# VoltageRegulationBoard.net
KiCad netlist of a schematic drawn in EAGLE
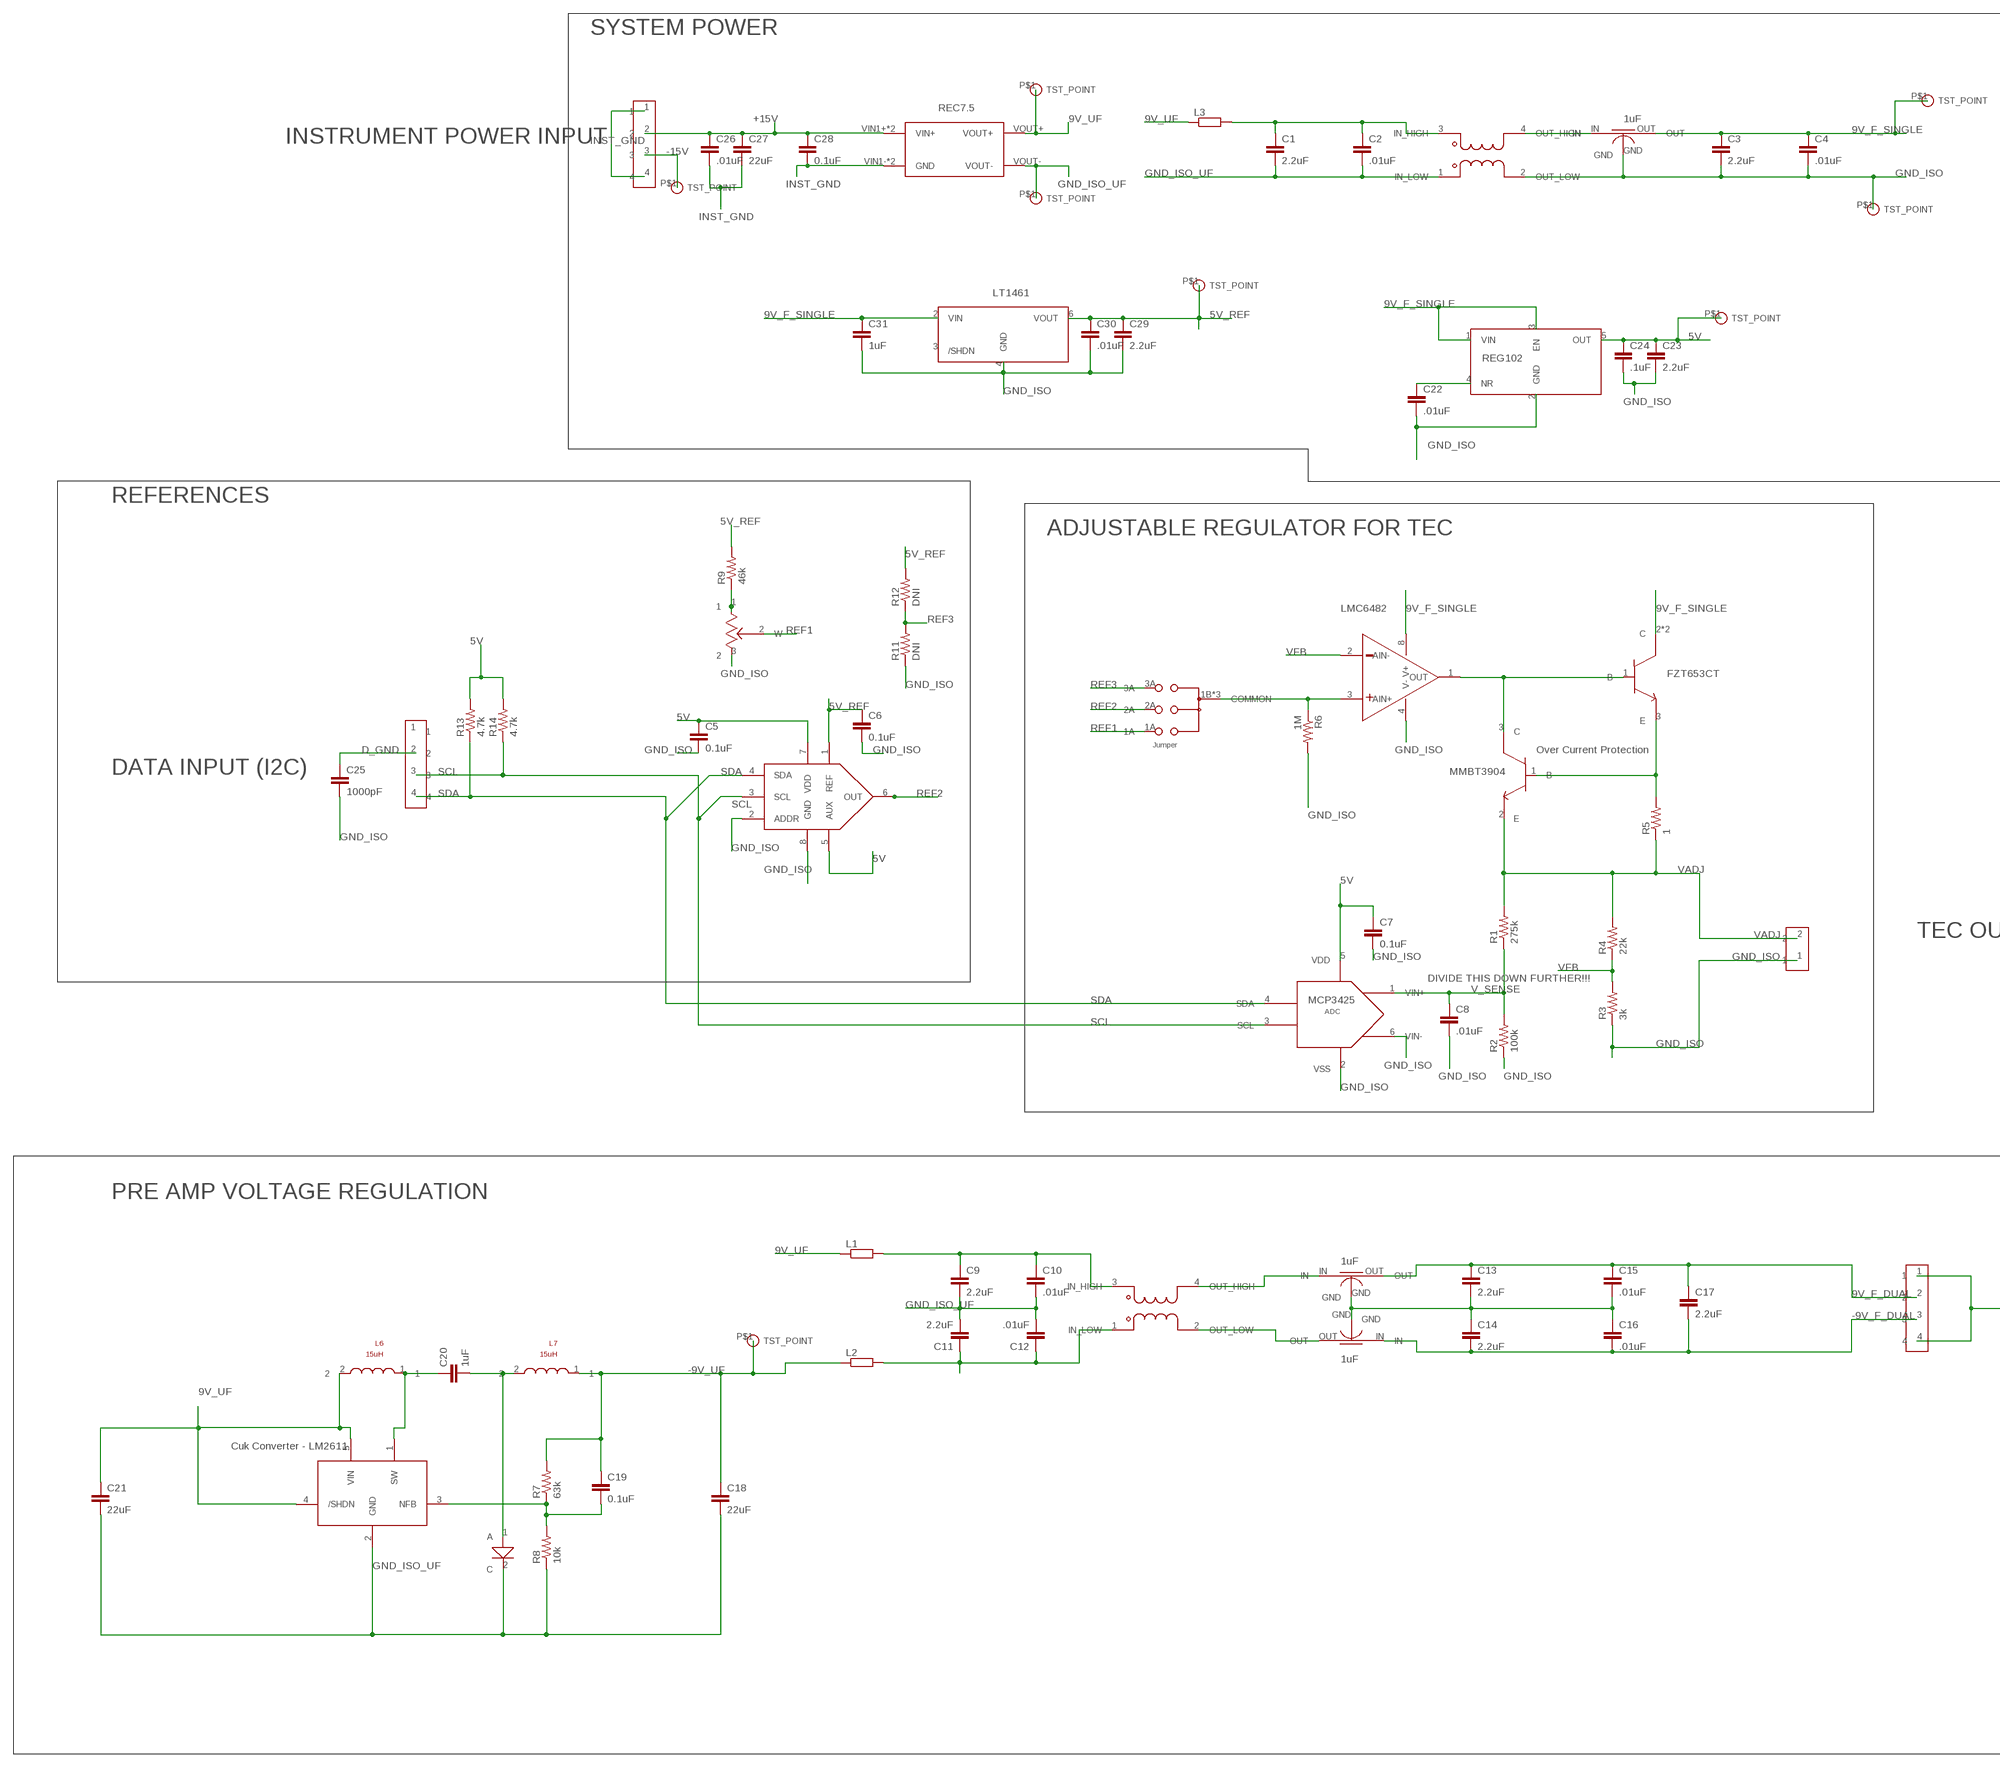
[diagram p0: schematic, sheet 1, part 1 of 2]
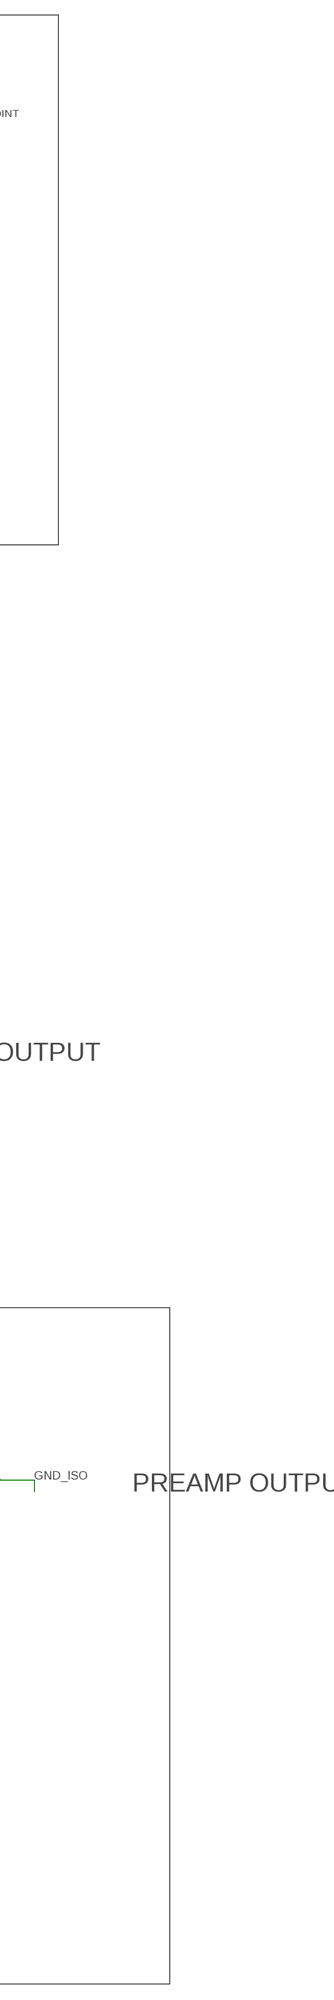
[diagram p1: schematic, sheet 1, part 2 of 2]

(export (version "E")
  (design (tool "Eeschema 10.0.6"))
  (components
    (comp (ref "-9V_U")
      (value "TST_PT")
      (footprint "eagle-import:TST_POINT")
      (libsource (lib "eagle-import") (part "TST_PT"))
    )
    (comp (ref "-15V")
      (value "TST_PT")
      (footprint "eagle-import:TST_POINT")
      (libsource (lib "eagle-import") (part "TST_PT"))
    )
    (comp (ref "5V")
      (value "TST_PT")
      (footprint "eagle-import:TST_POINT")
      (libsource (lib "eagle-import") (part "TST_PT"))
    )
    (comp (ref "9V_F_S")
      (value "TST_PT")
      (footprint "eagle-import:TST_POINT")
      (libsource (lib "eagle-import") (part "TST_PT"))
    )
    (comp (ref "9V_UF")
      (value "TST_PT")
      (footprint "eagle-import:TST_POINT")
      (libsource (lib "eagle-import") (part "TST_PT"))
    )
    (comp (ref "C1")
      (value "2.2uF")
      (footprint "eagle-import:C0603")
      (libsource (lib "eagle-import") (part "C-EUC0603"))
    )
    (comp (ref "C2")
      (value ".01uF")
      (footprint "eagle-import:C0603")
      (libsource (lib "eagle-import") (part "C-EUC0603"))
    )
    (comp (ref "C3")
      (value "2.2uF")
      (footprint "eagle-import:C0603")
      (libsource (lib "eagle-import") (part "C-EUC0603"))
    )
    (comp (ref "C4")
      (value ".01uF")
      (footprint "eagle-import:C0603")
      (libsource (lib "eagle-import") (part "C-EUC0603"))
    )
    (comp (ref "C5")
      (value "0.1uF")
      (footprint "eagle-import:C0603")
      (libsource (lib "eagle-import") (part "C-EUC0603"))
    )
    (comp (ref "C6")
      (value "0.1uF")
      (footprint "eagle-import:C0603")
      (libsource (lib "eagle-import") (part "C-EUC0603"))
    )
    (comp (ref "C7")
      (value "0.1uF")
      (footprint "eagle-import:C0603")
      (libsource (lib "eagle-import") (part "C-EUC0603"))
    )
    (comp (ref "C8")
      (value ".01uF")
      (footprint "eagle-import:C0603")
      (libsource (lib "eagle-import") (part "C-EUC0603"))
    )
    (comp (ref "C9")
      (value "2.2uF")
      (footprint "eagle-import:C0603")
      (libsource (lib "eagle-import") (part "C-EUC0603"))
    )
    (comp (ref "C10")
      (value ".01uF")
      (footprint "eagle-import:C0603")
      (libsource (lib "eagle-import") (part "C-EUC0603"))
    )
    (comp (ref "C11")
      (value "2.2uF")
      (footprint "eagle-import:C0603")
      (libsource (lib "eagle-import") (part "C-EUC0603"))
    )
    (comp (ref "C12")
      (value ".01uF")
      (footprint "eagle-import:C0603")
      (libsource (lib "eagle-import") (part "C-EUC0603"))
    )
    (comp (ref "C13")
      (value "2.2uF")
      (footprint "eagle-import:C0603")
      (libsource (lib "eagle-import") (part "C-EUC0603"))
    )
    (comp (ref "C14")
      (value "2.2uF")
      (footprint "eagle-import:C0603")
      (libsource (lib "eagle-import") (part "C-EUC0603"))
    )
    (comp (ref "C15")
      (value ".01uF")
      (footprint "eagle-import:C0603")
      (libsource (lib "eagle-import") (part "C-EUC0603"))
    )
    (comp (ref "C16")
      (value ".01uF")
      (footprint "eagle-import:C0603")
      (libsource (lib "eagle-import") (part "C-EUC0603"))
    )
    (comp (ref "C17")
      (value "2.2uF")
      (footprint "eagle-import:C0603")
      (libsource (lib "eagle-import") (part "C-EUC0603"))
    )
    (comp (ref "C18")
      (value "22uF")
      (footprint "eagle-import:C1206")
      (libsource (lib "eagle-import") (part "C-EUC1206"))
    )
    (comp (ref "C19")
      (value "0.1uF")
      (footprint "eagle-import:C0603")
      (libsource (lib "eagle-import") (part "C-EUC0603"))
    )
    (comp (ref "C20")
      (value "1uF")
      (footprint "eagle-import:C0603")
      (libsource (lib "eagle-import") (part "C-EUC0603"))
    )
    (comp (ref "C21")
      (value "22uF")
      (footprint "eagle-import:C1206")
      (libsource (lib "eagle-import") (part "C-EUC1206"))
    )
    (comp (ref "C22")
      (value ".01uF")
      (footprint "eagle-import:C0603")
      (libsource (lib "eagle-import") (part "C-EUC0603"))
    )
    (comp (ref "C23")
      (value "2.2uF")
      (footprint "eagle-import:C0603")
      (libsource (lib "eagle-import") (part "C-EUC0603"))
    )
    (comp (ref "C24")
      (value ".1uF")
      (footprint "eagle-import:C0603")
      (libsource (lib "eagle-import") (part "C-EUC0603"))
    )
    (comp (ref "C25")
      (value "1000pF")
      (footprint "eagle-import:C0603")
      (libsource (lib "eagle-import") (part "C-EUC0603"))
    )
    (comp (ref "C26")
      (value ".01uF")
      (footprint "eagle-import:C0603")
      (libsource (lib "eagle-import") (part "C-EUC0603"))
    )
    (comp (ref "C27")
      (value "22uF")
      (footprint "eagle-import:C1206")
      (libsource (lib "eagle-import") (part "C-EUC1206"))
    )
    (comp (ref "C28")
      (value "0.1uF")
      (footprint "eagle-import:C0603")
      (libsource (lib "eagle-import") (part "C-EUC0603"))
    )
    (comp (ref "C29")
      (value "2.2uF")
      (footprint "eagle-import:C0603")
      (libsource (lib "eagle-import") (part "C-EUC0603"))
    )
    (comp (ref "C30")
      (value ".01uF")
      (footprint "eagle-import:C0603")
      (libsource (lib "eagle-import") (part "C-EUC0603"))
    )
    (comp (ref "C31")
      (value "1uF")
      (footprint "eagle-import:C0603")
      (libsource (lib "eagle-import") (part "C-EUC0603"))
    )
    (comp (ref "FC1")
      (value "FEED_THRU_CAP")
      (footprint "eagle-import:3-TERM-CAP")
      (libsource (lib "eagle-import") (part "FEED_THRU_CAP"))
    )
    (comp (ref "FC2")
      (value "FEED_THRU_CAP")
      (footprint "eagle-import:3-TERM-CAP")
      (libsource (lib "eagle-import") (part "FEED_THRU_CAP"))
    )
    (comp (ref "FC3")
      (value "FEED_THRU_CAP")
      (footprint "eagle-import:3-TERM-CAP")
      (libsource (lib "eagle-import") (part "FEED_THRU_CAP"))
    )
    (comp (ref "GND_ISO")
      (value "TST_PT")
      (footprint "eagle-import:TST_POINT")
      (libsource (lib "eagle-import") (part "TST_PT"))
    )
    (comp (ref "GND_ISO_UF")
      (value "TST_PT")
      (footprint "eagle-import:TST_POINT")
      (libsource (lib "eagle-import") (part "TST_PT"))
    )
    (comp (ref "J1")
      (value "4-OUT")
      (footprint "eagle-import:4-THRU")
      (libsource (lib "eagle-import") (part "4-OUT"))
    )
    (comp (ref "J2")
      (value "4-OUT")
      (footprint "eagle-import:4-THRU")
      (libsource (lib "eagle-import") (part "4-OUT"))
    )
    (comp (ref "J3")
      (value "4-OUT")
      (footprint "eagle-import:4-THRU")
      (libsource (lib "eagle-import") (part "4-OUT"))
    )
    (comp (ref "J4")
      (value "2-THRU")
      (footprint "eagle-import:2-THRU-.1")
      (libsource (lib "eagle-import") (part "2-THRU"))
    )
    (comp (ref "L1")
      (value "R-EU_R0603")
      (footprint "eagle-import:R0603")
      (libsource (lib "eagle-import") (part "R-EU_R0603"))
    )
    (comp (ref "L2")
      (value "R-EU_R0603")
      (footprint "eagle-import:R0603")
      (libsource (lib "eagle-import") (part "R-EU_R0603"))
    )
    (comp (ref "L3")
      (value "R-EU_R0603")
      (footprint "eagle-import:R0603")
      (libsource (lib "eagle-import") (part "R-EU_R0603"))
    )
    (comp (ref "L4")
      (value "COMMON_MODE_CHOKE")
      (footprint "eagle-import:COMM_MODE_CHOKE")
      (libsource (lib "eagle-import") (part "COMMON_MODE_CHOKE"))
    )
    (comp (ref "L5")
      (value "COMMON_MODE_CHOKE")
      (footprint "eagle-import:COMM_MODE_CHOKE")
      (libsource (lib "eagle-import") (part "COMMON_MODE_CHOKE"))
    )
    (comp (ref "L6")
      (value "15uH")
      (footprint "eagle-import:INDUCTOR_FOOTPRNT")
      (libsource (lib "eagle-import") (part "INDUCTOR"))
    )
    (comp (ref "L7")
      (value "15uH")
      (footprint "eagle-import:INDUCTOR_FOOTPRNT")
      (libsource (lib "eagle-import") (part "INDUCTOR"))
    )
    (comp (ref "R1")
      (value "275k")
      (footprint "eagle-import:R0603")
      (libsource (lib "eagle-import") (part "R-US_R0603"))
    )
    (comp (ref "R2")
      (value "100k")
      (footprint "eagle-import:R0603")
      (libsource (lib "eagle-import") (part "R-US_R0603"))
    )
    (comp (ref "R3")
      (value "3k")
      (footprint "eagle-import:R0603")
      (libsource (lib "eagle-import") (part "R-US_R0603"))
    )
    (comp (ref "R4")
      (value "22k")
      (footprint "eagle-import:R0603")
      (libsource (lib "eagle-import") (part "R-US_R0603"))
    )
    (comp (ref "R5")
      (value "1")
      (footprint "eagle-import:R2512")
      (libsource (lib "eagle-import") (part "R-US_R2512"))
    )
    (comp (ref "R6")
      (value "1M")
      (footprint "eagle-import:R0603")
      (libsource (lib "eagle-import") (part "R-US_R0603"))
    )
    (comp (ref "R7")
      (value "63k")
      (footprint "eagle-import:R0603")
      (libsource (lib "eagle-import") (part "R-US_R0603"))
    )
    (comp (ref "R8")
      (value "10k")
      (footprint "eagle-import:R0603")
      (libsource (lib "eagle-import") (part "R-US_R0603"))
    )
    (comp (ref "R9")
      (value "46k")
      (footprint "eagle-import:R0603")
      (libsource (lib "eagle-import") (part "R-US_R0603"))
    )
    (comp (ref "R10")
      (value "POTENTIOMETER")
      (footprint "eagle-import:3-THRU")
      (libsource (lib "eagle-import") (part "POTENTIOMETER"))
    )
    (comp (ref "R11")
      (value "DNI")
      (footprint "eagle-import:R0603")
      (libsource (lib "eagle-import") (part "R-US_R0603"))
    )
    (comp (ref "R12")
      (value "DNI")
      (footprint "eagle-import:R0603")
      (libsource (lib "eagle-import") (part "R-US_R0603"))
    )
    (comp (ref "R13")
      (value "4.7k")
      (footprint "eagle-import:R0603")
      (libsource (lib "eagle-import") (part "R-US_R0603"))
    )
    (comp (ref "R14")
      (value "4.7k")
      (footprint "eagle-import:R0603")
      (libsource (lib "eagle-import") (part "R-US_R0603"))
    )
    (comp (ref "T1")
      (value "MMBT3904LT1GOSCT-ND(SMALL-SIGNAL-NMOS)")
      (footprint "eagle-import:SOT23")
      (libsource (lib "eagle-import") (part "MMBT3904LT1GOSCT-ND(SMALL-SIGNAL-NMOS)"))
    )
    (comp (ref "T2")
      (value "FZT653-NPNBJT")
      (footprint "eagle-import:SOT223")
      (libsource (lib "eagle-import") (part "FZT653-NPNBJT"))
    )
    (comp (ref "U$3")
      (value "3XJUMPER")
      (footprint "eagle-import:2-THRU")
      (libsource (lib "eagle-import") (part "3XJUMPER"))
    )
    (comp (ref "U$10")
      (value "SCHOTTKY")
      (footprint "eagle-import:SOD-123")
      (libsource (lib "eagle-import") (part "SCHOTTKY"))
    )
    (comp (ref "U1")
      (value "LMC6482")
      (footprint "eagle-import:SOIC8")
      (libsource (lib "eagle-import") (part "LMC6482"))
    )
    (comp (ref "U2")
      (value "DAC_UMAX")
      (footprint "eagle-import:8-UMAX")
      (libsource (lib "eagle-import") (part "DAC_UMAX"))
    )
    (comp (ref "U3")
      (value "VREF")
      (footprint "eagle-import:SOIC8")
      (libsource (lib "eagle-import") (part "VREF"))
    )
    (comp (ref "U4")
      (value "REC7.5-1209")
      (footprint "eagle-import:REC7.5-1209")
      (libsource (lib "eagle-import") (part "REC7.5-1209"))
    )
    (comp (ref "U5")
      (value "REG102")
      (footprint "eagle-import:SOT-23-5")
      (libsource (lib "eagle-import") (part "REG102"))
    )
    (comp (ref "U6")
      (value "MCP3425A0T-E")
      (footprint "eagle-import:SOT-23-6")
      (libsource (lib "eagle-import") (part "MCP3425A0T-E"))
    )
    (comp (ref "U7")
      (value "LM2611")
      (footprint "eagle-import:SOT-23-5")
      (libsource (lib "eagle-import") (part "LM2611"))
    )
    (comp (ref "VREF")
      (value "TST_PT")
      (footprint "eagle-import:TST_POINT")
      (libsource (lib "eagle-import") (part "TST_PT"))
    )
  )
  (nets
    (net (code "1") (name "/+15V") (class "Default")
      (node (ref "C26") (pin "1") (pinfunction "1_1") (pintype "passive"))
      (node (ref "C27") (pin "1") (pinfunction "1_1") (pintype "passive"))
      (node (ref "C28") (pin "1") (pinfunction "1_1") (pintype "passive"))
      (node (ref "J1") (pin "2") (pinfunction "2_2") (pintype "bidirectional"))
      (node (ref "U4") (pin "VIN1+") (pinfunction "VIN+_VIN1+") (pintype "bidirectional"))
      (node (ref "U4") (pin "VIN2+") (pinfunction "VIN+_VIN2+") (pintype "bidirectional"))
    )
    (net (code "2") (name "/-9V_F_DUAL") (class "Default")
      (node (ref "C14") (pin "2") (pinfunction "2_2") (pintype "passive"))
      (node (ref "C16") (pin "2") (pinfunction "2_2") (pintype "passive"))
      (node (ref "C17") (pin "2") (pinfunction "2_2") (pintype "passive"))
      (node (ref "FC1") (pin "IN") (pinfunction "IN_IN") (pintype "bidirectional"))
      (node (ref "J2") (pin "3") (pinfunction "3_3") (pintype "bidirectional"))
    )
    (net (code "3") (name "/-9V_UF") (class "Default")
      (node (ref "-9V_U") (pin "P$1") (pinfunction "TST_POINT_P$1") (pintype "bidirectional"))
      (node (ref "C18") (pin "1") (pinfunction "1_1") (pintype "passive"))
      (node (ref "C19") (pin "1") (pinfunction "1_1") (pintype "passive"))
      (node (ref "L2") (pin "1") (pinfunction "1_1") (pintype "passive"))
      (node (ref "L7") (pin "1") (pinfunction "1_1") (pintype "bidirectional"))
      (node (ref "R7") (pin "2") (pinfunction "2_2") (pintype "passive"))
    )
    (net (code "4") (name "/-15V") (class "Default")
      (node (ref "-15V") (pin "P$1") (pinfunction "TST_POINT_P$1") (pintype "bidirectional"))
      (node (ref "J1") (pin "3") (pinfunction "3_3") (pintype "bidirectional"))
    )
    (net (code "5") (name "/5V") (class "Default")
      (node (ref "5V") (pin "P$1") (pinfunction "TST_POINT_P$1") (pintype "bidirectional"))
      (node (ref "C23") (pin "1") (pinfunction "1_1") (pintype "passive"))
      (node (ref "C24") (pin "1") (pinfunction "1_1") (pintype "passive"))
      (node (ref "C5") (pin "1") (pinfunction "1_1") (pintype "passive"))
      (node (ref "C7") (pin "1") (pinfunction "1_1") (pintype "passive"))
      (node (ref "R13") (pin "2") (pinfunction "2_2") (pintype "passive"))
      (node (ref "R14") (pin "2") (pinfunction "2_2") (pintype "passive"))
      (node (ref "U2") (pin "5") (pinfunction "AUX_5") (pintype "bidirectional"))
      (node (ref "U2") (pin "7") (pinfunction "VDD_7") (pintype "bidirectional"))
      (node (ref "U5") (pin "5") (pinfunction "OUT_5") (pintype "bidirectional"))
      (node (ref "U6") (pin "5") (pinfunction "VDD_5") (pintype "bidirectional"))
    )
    (net (code "6") (name "/5V_REF") (class "Default")
      (node (ref "C29") (pin "1") (pinfunction "1_1") (pintype "passive"))
      (node (ref "C30") (pin "1") (pinfunction "1_1") (pintype "passive"))
      (node (ref "C6") (pin "1") (pinfunction "1_1") (pintype "passive"))
      (node (ref "R12") (pin "2") (pinfunction "2_2") (pintype "passive"))
      (node (ref "R9") (pin "2") (pinfunction "2_2") (pintype "passive"))
      (node (ref "U2") (pin "1") (pinfunction "REF_1") (pintype "bidirectional"))
      (node (ref "U3") (pin "6") (pinfunction "VOUT_6") (pintype "bidirectional"))
      (node (ref "VREF") (pin "P$1") (pinfunction "TST_POINT_P$1") (pintype "bidirectional"))
    )
    (net (code "7") (name "/9V_F_DUAL") (class "Default")
      (node (ref "C13") (pin "1") (pinfunction "1_1") (pintype "passive"))
      (node (ref "C15") (pin "1") (pinfunction "1_1") (pintype "passive"))
      (node (ref "C17") (pin "1") (pinfunction "1_1") (pintype "passive"))
      (node (ref "FC2") (pin "OUT") (pinfunction "OUT_OUT") (pintype "bidirectional"))
      (node (ref "J2") (pin "2") (pinfunction "2_2") (pintype "bidirectional"))
    )
    (net (code "8") (name "/9V_F_SINGLE") (class "Default")
      (node (ref "9V_F_S") (pin "P$1") (pinfunction "TST_POINT_P$1") (pintype "bidirectional"))
      (node (ref "C3") (pin "1") (pinfunction "1_1") (pintype "passive"))
      (node (ref "C31") (pin "1") (pinfunction "1_1") (pintype "passive"))
      (node (ref "C4") (pin "1") (pinfunction "1_1") (pintype "passive"))
      (node (ref "FC3") (pin "OUT") (pinfunction "OUT_OUT") (pintype "bidirectional"))
      (node (ref "T2") (pin "2") (pinfunction "C_2") (pintype "bidirectional"))
      (node (ref "T2") (pin "4") (pinfunction "C_4") (pintype "bidirectional"))
      (node (ref "U1") (pin "8") (pinfunction "V+_8") (pintype "bidirectional"))
      (node (ref "U3") (pin "2") (pinfunction "VIN_2") (pintype "bidirectional"))
      (node (ref "U5") (pin "1") (pinfunction "VIN_1") (pintype "bidirectional"))
      (node (ref "U5") (pin "3") (pinfunction "EN_3") (pintype "bidirectional"))
    )
    (net (code "9") (name "/9V_UF") (class "Default")
      (node (ref "9V_UF") (pin "P$1") (pinfunction "TST_POINT_P$1") (pintype "bidirectional"))
      (node (ref "C21") (pin "1") (pinfunction "1_1") (pintype "passive"))
      (node (ref "L1") (pin "1") (pinfunction "1_1") (pintype "passive"))
      (node (ref "L3") (pin "1") (pinfunction "1_1") (pintype "passive"))
      (node (ref "L6") (pin "2") (pinfunction "2_2") (pintype "bidirectional"))
      (node (ref "U4") (pin "VOUT+") (pinfunction "VOUT+_VOUT+") (pintype "bidirectional"))
      (node (ref "U7") (pin "4") (pinfunction "/SHDN_4") (pintype "bidirectional"))
      (node (ref "U7") (pin "5") (pinfunction "VIN_5") (pintype "bidirectional"))
    )
    (net (code "10") (name "/D_GND") (class "Default")
      (node (ref "C25") (pin "1") (pinfunction "1_1") (pintype "passive"))
      (node (ref "J3") (pin "2") (pinfunction "2_2") (pintype "bidirectional"))
    )
    (net (code "11") (name "/GND_ISO") (class "Default")
      (node (ref "C13") (pin "2") (pinfunction "2_2") (pintype "passive"))
      (node (ref "C14") (pin "1") (pinfunction "1_1") (pintype "passive"))
      (node (ref "C15") (pin "2") (pinfunction "2_2") (pintype "passive"))
      (node (ref "C16") (pin "1") (pinfunction "1_1") (pintype "passive"))
      (node (ref "C22") (pin "2") (pinfunction "2_2") (pintype "passive"))
      (node (ref "C23") (pin "2") (pinfunction "2_2") (pintype "passive"))
      (node (ref "C24") (pin "2") (pinfunction "2_2") (pintype "passive"))
      (node (ref "C25") (pin "2") (pinfunction "2_2") (pintype "passive"))
      (node (ref "C29") (pin "2") (pinfunction "2_2") (pintype "passive"))
      (node (ref "C3") (pin "2") (pinfunction "2_2") (pintype "passive"))
      (node (ref "C30") (pin "2") (pinfunction "2_2") (pintype "passive"))
      (node (ref "C31") (pin "2") (pinfunction "2_2") (pintype "passive"))
      (node (ref "C4") (pin "2") (pinfunction "2_2") (pintype "passive"))
      (node (ref "C5") (pin "2") (pinfunction "2_2") (pintype "passive"))
      (node (ref "C6") (pin "2") (pinfunction "2_2") (pintype "passive"))
      (node (ref "C7") (pin "2") (pinfunction "2_2") (pintype "passive"))
      (node (ref "C8") (pin "2") (pinfunction "2_2") (pintype "passive"))
      (node (ref "FC1") (pin "GND") (pinfunction "GND_GND") (pintype "bidirectional"))
      (node (ref "FC2") (pin "GND") (pinfunction "GND_GND") (pintype "bidirectional"))
      (node (ref "FC3") (pin "GND") (pinfunction "GND_GND") (pintype "bidirectional"))
      (node (ref "GND_ISO") (pin "P$1") (pinfunction "TST_POINT_P$1") (pintype "bidirectional"))
      (node (ref "J2") (pin "1") (pinfunction "1_1") (pintype "bidirectional"))
      (node (ref "J2") (pin "4") (pinfunction "4_4") (pintype "bidirectional"))
      (node (ref "J4") (pin "1") (pinfunction "1_1") (pintype "bidirectional"))
      (node (ref "L5") (pin "2") (pinfunction "OUT_LOW_2") (pintype "bidirectional"))
      (node (ref "R10") (pin "3") (pinfunction "2_3") (pintype "bidirectional"))
      (node (ref "R11") (pin "1") (pinfunction "1_1") (pintype "passive"))
      (node (ref "R2") (pin "1") (pinfunction "1_1") (pintype "passive"))
      (node (ref "R3") (pin "1") (pinfunction "1_1") (pintype "passive"))
      (node (ref "R6") (pin "2") (pinfunction "2_2") (pintype "passive"))
      (node (ref "U1") (pin "4") (pinfunction "V-_4") (pintype "bidirectional"))
      (node (ref "U2") (pin "2") (pinfunction "ADDR_2") (pintype "bidirectional"))
      (node (ref "U2") (pin "8") (pinfunction "GND_8") (pintype "bidirectional"))
      (node (ref "U3") (pin "4") (pinfunction "GND_4") (pintype "bidirectional"))
      (node (ref "U5") (pin "2") (pinfunction "GND_2") (pintype "bidirectional"))
      (node (ref "U6") (pin "2") (pinfunction "VSS_2") (pintype "bidirectional"))
      (node (ref "U6") (pin "6") (pinfunction "VIN-_6") (pintype "bidirectional"))
    )
    (net (code "12") (name "/GND_ISO_UF") (class "Default")
      (node (ref "C1") (pin "2") (pinfunction "2_2") (pintype "passive"))
      (node (ref "C10") (pin "2") (pinfunction "2_2") (pintype "passive"))
      (node (ref "C11") (pin "2") (pinfunction "2_2") (pintype "passive"))
      (node (ref "C12") (pin "2") (pinfunction "2_2") (pintype "passive"))
      (node (ref "C18") (pin "2") (pinfunction "2_2") (pintype "passive"))
      (node (ref "C2") (pin "2") (pinfunction "2_2") (pintype "passive"))
      (node (ref "C21") (pin "2") (pinfunction "2_2") (pintype "passive"))
      (node (ref "C9") (pin "2") (pinfunction "2_2") (pintype "passive"))
      (node (ref "GND_ISO_UF") (pin "P$1") (pinfunction "TST_POINT_P$1") (pintype "bidirectional"))
      (node (ref "L5") (pin "1") (pinfunction "IN_LOW_1") (pintype "bidirectional"))
      (node (ref "R8") (pin "1") (pinfunction "1_1") (pintype "passive"))
      (node (ref "U$10") (pin "2") (pinfunction "C_2") (pintype "bidirectional"))
      (node (ref "U4") (pin "VOUT-") (pinfunction "VOUT-_VOUT-") (pintype "bidirectional"))
      (node (ref "U7") (pin "2") (pinfunction "GND_2") (pintype "bidirectional"))
    )
    (net (code "13") (name "/INST_GND") (class "Default")
      (node (ref "C26") (pin "2") (pinfunction "2_2") (pintype "passive"))
      (node (ref "C27") (pin "2") (pinfunction "2_2") (pintype "passive"))
      (node (ref "C28") (pin "2") (pinfunction "2_2") (pintype "passive"))
      (node (ref "J1") (pin "1") (pinfunction "1_1") (pintype "bidirectional"))
      (node (ref "J1") (pin "4") (pinfunction "4_4") (pintype "bidirectional"))
      (node (ref "U4") (pin "VIN1-") (pinfunction "GND_VIN1-") (pintype "bidirectional"))
      (node (ref "U4") (pin "VIN2-") (pinfunction "GND_VIN2-") (pintype "bidirectional"))
    )
    (net (code "14") (name "/REF1") (class "Default")
      (node (ref "R10") (pin "2") (pinfunction "W_2") (pintype "bidirectional"))
      (node (ref "U$3") (pin "1A") (pinfunction "1A_1A") (pintype "bidirectional"))
    )
    (net (code "15") (name "/REF2") (class "Default")
      (node (ref "U$3") (pin "2A") (pinfunction "2A_2A") (pintype "bidirectional"))
      (node (ref "U2") (pin "6") (pinfunction "OUT_6") (pintype "bidirectional"))
    )
    (net (code "16") (name "/REF3") (class "Default")
      (node (ref "R11") (pin "2") (pinfunction "2_2") (pintype "passive"))
      (node (ref "R12") (pin "1") (pinfunction "1_1") (pintype "passive"))
      (node (ref "U$3") (pin "3A") (pinfunction "3A_3A") (pintype "bidirectional"))
    )
    (net (code "17") (name "/SCL") (class "Default")
      (node (ref "J3") (pin "3") (pinfunction "3_3") (pintype "bidirectional"))
      (node (ref "R14") (pin "1") (pinfunction "1_1") (pintype "passive"))
      (node (ref "U2") (pin "3") (pinfunction "SCL_3") (pintype "bidirectional"))
      (node (ref "U6") (pin "3") (pinfunction "SCL_3") (pintype "bidirectional"))
    )
    (net (code "18") (name "/SDA") (class "Default")
      (node (ref "J3") (pin "4") (pinfunction "4_4") (pintype "bidirectional"))
      (node (ref "R13") (pin "1") (pinfunction "1_1") (pintype "passive"))
      (node (ref "U2") (pin "4") (pinfunction "SDA_4") (pintype "bidirectional"))
      (node (ref "U6") (pin "4") (pinfunction "SDA_4") (pintype "bidirectional"))
    )
    (net (code "19") (name "/VADJ") (class "Default")
      (node (ref "J4") (pin "2") (pinfunction "2_2") (pintype "bidirectional"))
      (node (ref "R1") (pin "2") (pinfunction "2_2") (pintype "passive"))
      (node (ref "R4") (pin "2") (pinfunction "2_2") (pintype "passive"))
      (node (ref "R5") (pin "1") (pinfunction "1_1") (pintype "passive"))
      (node (ref "T1") (pin "2") (pinfunction "E_2") (pintype "bidirectional"))
    )
    (net (code "20") (name "/VFB") (class "Default")
      (node (ref "R3") (pin "2") (pinfunction "2_2") (pintype "passive"))
      (node (ref "R4") (pin "1") (pinfunction "1_1") (pintype "passive"))
      (node (ref "U1") (pin "2") (pinfunction "AIN-_2") (pintype "bidirectional"))
    )
    (net (code "21") (name "/V_SENSE") (class "Default")
      (node (ref "C8") (pin "1") (pinfunction "1_1") (pintype "passive"))
      (node (ref "R1") (pin "1") (pinfunction "1_1") (pintype "passive"))
      (node (ref "R2") (pin "2") (pinfunction "2_2") (pintype "passive"))
      (node (ref "U6") (pin "1") (pinfunction "VIN+_1") (pintype "bidirectional"))
    )
    (net (code "22") (name "Net-(L4-IN_HIGH)") (class "Default")
      (node (ref "C10") (pin "1") (pinfunction "1_1") (pintype "passive"))
      (node (ref "C9") (pin "1") (pinfunction "1_1") (pintype "passive"))
      (node (ref "L1") (pin "2") (pinfunction "2_2") (pintype "passive"))
      (node (ref "L4") (pin "3") (pinfunction "IN_HIGH_3") (pintype "bidirectional"))
    )
    (net (code "23") (name "Net-(L4-IN_LOW)") (class "Default")
      (node (ref "C11") (pin "1") (pinfunction "1_1") (pintype "passive"))
      (node (ref "C12") (pin "1") (pinfunction "1_1") (pintype "passive"))
      (node (ref "L2") (pin "2") (pinfunction "2_2") (pintype "passive"))
      (node (ref "L4") (pin "1") (pinfunction "IN_LOW_1") (pintype "bidirectional"))
    )
    (net (code "24") (name "Net-(L4-OUT_HIGH)") (class "Default")
      (node (ref "FC2") (pin "IN") (pinfunction "IN_IN") (pintype "bidirectional"))
      (node (ref "L4") (pin "4") (pinfunction "OUT_HIGH_4") (pintype "bidirectional"))
    )
    (net (code "25") (name "Net-(L4-OUT_LOW)") (class "Default")
      (node (ref "FC1") (pin "OUT") (pinfunction "OUT_OUT") (pintype "bidirectional"))
      (node (ref "L4") (pin "2") (pinfunction "OUT_LOW_2") (pintype "bidirectional"))
    )
    (net (code "26") (name "Net-(L5-IN_HIGH)") (class "Default")
      (node (ref "C1") (pin "1") (pinfunction "1_1") (pintype "passive"))
      (node (ref "C2") (pin "1") (pinfunction "1_1") (pintype "passive"))
      (node (ref "L3") (pin "2") (pinfunction "2_2") (pintype "passive"))
      (node (ref "L5") (pin "3") (pinfunction "IN_HIGH_3") (pintype "bidirectional"))
    )
    (net (code "27") (name "Net-(L5-OUT_HIGH)") (class "Default")
      (node (ref "FC3") (pin "IN") (pinfunction "IN_IN") (pintype "bidirectional"))
      (node (ref "L5") (pin "4") (pinfunction "OUT_HIGH_4") (pintype "bidirectional"))
    )
    (net (code "28") (name "Net-(R10-Pad1)") (class "Default")
      (node (ref "R10") (pin "1") (pinfunction "1_1") (pintype "bidirectional"))
      (node (ref "R9") (pin "1") (pinfunction "1_1") (pintype "passive"))
    )
    (net (code "29") (name "Net-(T1-B)") (class "Default")
      (node (ref "R5") (pin "2") (pinfunction "2_2") (pintype "passive"))
      (node (ref "T1") (pin "1") (pinfunction "B_1") (pintype "bidirectional"))
      (node (ref "T2") (pin "3") (pinfunction "E_3") (pintype "bidirectional"))
    )
    (net (code "30") (name "Net-(T1-C)") (class "Default")
      (node (ref "T1") (pin "3") (pinfunction "C_3") (pintype "bidirectional"))
      (node (ref "T2") (pin "1") (pinfunction "B_1") (pintype "bidirectional"))
      (node (ref "U1") (pin "1") (pinfunction "OUT_1") (pintype "bidirectional"))
    )
    (net (code "31") (name "Net-(U$10-A)") (class "Default")
      (node (ref "C20") (pin "2") (pinfunction "2_2") (pintype "passive"))
      (node (ref "L7") (pin "2") (pinfunction "2_2") (pintype "bidirectional"))
      (node (ref "U$10") (pin "1") (pinfunction "A_1") (pintype "bidirectional"))
    )
    (net (code "32") (name "Net-(U1A-AIN+)") (class "Default")
      (node (ref "R6") (pin "1") (pinfunction "1_1") (pintype "passive"))
      (node (ref "U$3") (pin "1B") (pinfunction "COMMON_1B") (pintype "bidirectional"))
      (node (ref "U$3") (pin "2B") (pinfunction "COMMON_2B") (pintype "bidirectional"))
      (node (ref "U$3") (pin "3B") (pinfunction "COMMON_3B") (pintype "bidirectional"))
      (node (ref "U1") (pin "3") (pinfunction "AIN+_3") (pintype "bidirectional"))
    )
    (net (code "33") (name "Net-(U5-NR)") (class "Default")
      (node (ref "C22") (pin "1") (pinfunction "1_1") (pintype "passive"))
      (node (ref "U5") (pin "4") (pinfunction "NR_4") (pintype "bidirectional"))
    )
    (net (code "34") (name "Net-(U7-NFB)") (class "Default")
      (node (ref "C19") (pin "2") (pinfunction "2_2") (pintype "passive"))
      (node (ref "R7") (pin "1") (pinfunction "1_1") (pintype "passive"))
      (node (ref "R8") (pin "2") (pinfunction "2_2") (pintype "passive"))
      (node (ref "U7") (pin "3") (pinfunction "NFB_3") (pintype "bidirectional"))
    )
    (net (code "35") (name "Net-(U7-SW)") (class "Default")
      (node (ref "C20") (pin "1") (pinfunction "1_1") (pintype "passive"))
      (node (ref "L6") (pin "1") (pinfunction "1_1") (pintype "bidirectional"))
      (node (ref "U7") (pin "1") (pinfunction "SW_1") (pintype "bidirectional"))
    )
    (net (code "36") (name "unconnected-(J3-Pad1)") (class "Default")
      (node (ref "J3") (pin "1") (pinfunction "1_1") (pintype "bidirectional"))
    )
    (net (code "37") (name "unconnected-(U3-{slash}SHDN-Pad3)") (class "Default")
      (node (ref "U3") (pin "3") (pinfunction "/SHDN_3") (pintype "bidirectional"))
    )
  )
)
